# LED.net
KiCad netlist of a schematic drawn in EAGLE
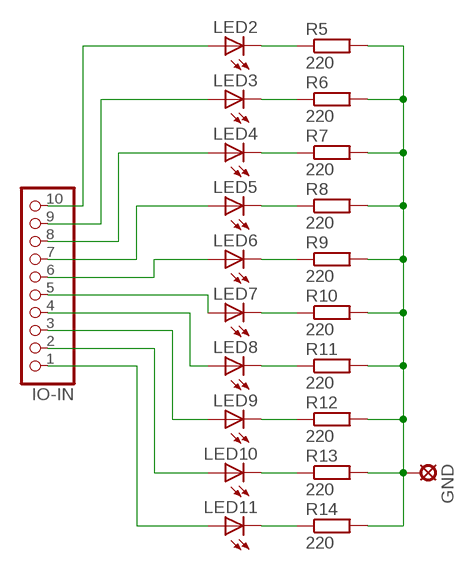
[diagram p0: schematic, sheet 1]

(export (version "E")
  (design (tool "Eeschema 10.0.6"))
  (components
    (comp (ref "GND")
      (value "LSP10")
      (footprint "eagle-import:LSP10")
      (libsource (lib "eagle-import") (part "LSP10"))
    )
    (comp (ref "IO-IN")
      (value "PINHD-1X10")
      (footprint "eagle-import:1X10")
      (libsource (lib "eagle-import") (part "PINHD-1X10"))
    )
    (comp (ref "LED2")
      (value "LED3MM")
      (footprint "eagle-import:LED3MM")
      (libsource (lib "eagle-import") (part "LED3MM"))
    )
    (comp (ref "LED3")
      (value "LED3MM")
      (footprint "eagle-import:LED3MM")
      (libsource (lib "eagle-import") (part "LED3MM"))
    )
    (comp (ref "LED4")
      (value "LED3MM")
      (footprint "eagle-import:LED3MM")
      (libsource (lib "eagle-import") (part "LED3MM"))
    )
    (comp (ref "LED5")
      (value "LED3MM")
      (footprint "eagle-import:LED3MM")
      (libsource (lib "eagle-import") (part "LED3MM"))
    )
    (comp (ref "LED6")
      (value "LED3MM")
      (footprint "eagle-import:LED3MM")
      (libsource (lib "eagle-import") (part "LED3MM"))
    )
    (comp (ref "LED7")
      (value "LED3MM")
      (footprint "eagle-import:LED3MM")
      (libsource (lib "eagle-import") (part "LED3MM"))
    )
    (comp (ref "LED8")
      (value "LED3MM")
      (footprint "eagle-import:LED3MM")
      (libsource (lib "eagle-import") (part "LED3MM"))
    )
    (comp (ref "LED9")
      (value "LED3MM")
      (footprint "eagle-import:LED3MM")
      (libsource (lib "eagle-import") (part "LED3MM"))
    )
    (comp (ref "LED10")
      (value "LED3MM")
      (footprint "eagle-import:LED3MM")
      (libsource (lib "eagle-import") (part "LED3MM"))
    )
    (comp (ref "LED11")
      (value "LED3MM")
      (footprint "eagle-import:LED3MM")
      (libsource (lib "eagle-import") (part "LED3MM"))
    )
    (comp (ref "R5")
      (value "220")
      (footprint "eagle-import:0207_10")
      (libsource (lib "eagle-import") (part "R-EU_0207/10"))
    )
    (comp (ref "R6")
      (value "220")
      (footprint "eagle-import:0207_10")
      (libsource (lib "eagle-import") (part "R-EU_0207/10"))
    )
    (comp (ref "R7")
      (value "220")
      (footprint "eagle-import:0207_10")
      (libsource (lib "eagle-import") (part "R-EU_0207/10"))
    )
    (comp (ref "R8")
      (value "220")
      (footprint "eagle-import:0207_10")
      (libsource (lib "eagle-import") (part "R-EU_0207/10"))
    )
    (comp (ref "R9")
      (value "220")
      (footprint "eagle-import:0207_10")
      (libsource (lib "eagle-import") (part "R-EU_0207/10"))
    )
    (comp (ref "R10")
      (value "220")
      (footprint "eagle-import:0207_10")
      (libsource (lib "eagle-import") (part "R-EU_0207/10"))
    )
    (comp (ref "R11")
      (value "220")
      (footprint "eagle-import:0207_10")
      (libsource (lib "eagle-import") (part "R-EU_0207/10"))
    )
    (comp (ref "R12")
      (value "220")
      (footprint "eagle-import:0207_10")
      (libsource (lib "eagle-import") (part "R-EU_0207/10"))
    )
    (comp (ref "R13")
      (value "220")
      (footprint "eagle-import:0207_10")
      (libsource (lib "eagle-import") (part "R-EU_0207/10"))
    )
    (comp (ref "R14")
      (value "220")
      (footprint "eagle-import:0207_10")
      (libsource (lib "eagle-import") (part "R-EU_0207/10"))
    )
  )
  (nets
    (net (code "1") (name "Net-(GND-PadMP)") (class "Default")
      (node (ref "GND") (pin "MP") (pinfunction "MP_MP") (pintype "passive"))
      (node (ref "R10") (pin "2") (pinfunction "2_2") (pintype "passive"))
      (node (ref "R11") (pin "2") (pinfunction "2_2") (pintype "passive"))
      (node (ref "R12") (pin "2") (pinfunction "2_2") (pintype "passive"))
      (node (ref "R13") (pin "2") (pinfunction "2_2") (pintype "passive"))
      (node (ref "R14") (pin "2") (pinfunction "2_2") (pintype "passive"))
      (node (ref "R5") (pin "2") (pinfunction "2_2") (pintype "passive"))
      (node (ref "R6") (pin "2") (pinfunction "2_2") (pintype "passive"))
      (node (ref "R7") (pin "2") (pinfunction "2_2") (pintype "passive"))
      (node (ref "R8") (pin "2") (pinfunction "2_2") (pintype "passive"))
      (node (ref "R9") (pin "2") (pinfunction "2_2") (pintype "passive"))
    )
    (net (code "2") (name "Net-(IO-IN-Pad1)") (class "Default")
      (node (ref "IO-IN") (pin "1") (pinfunction "1_1") (pintype "passive"))
      (node (ref "LED11") (pin "A") (pinfunction "A_A") (pintype "passive"))
    )
    (net (code "3") (name "Net-(IO-IN-Pad2)") (class "Default")
      (node (ref "IO-IN") (pin "2") (pinfunction "2_2") (pintype "passive"))
      (node (ref "LED10") (pin "A") (pinfunction "A_A") (pintype "passive"))
    )
    (net (code "4") (name "Net-(IO-IN-Pad3)") (class "Default")
      (node (ref "IO-IN") (pin "3") (pinfunction "3_3") (pintype "passive"))
      (node (ref "LED9") (pin "A") (pinfunction "A_A") (pintype "passive"))
    )
    (net (code "5") (name "Net-(IO-IN-Pad4)") (class "Default")
      (node (ref "IO-IN") (pin "4") (pinfunction "4_4") (pintype "passive"))
      (node (ref "LED8") (pin "A") (pinfunction "A_A") (pintype "passive"))
    )
    (net (code "6") (name "Net-(IO-IN-Pad5)") (class "Default")
      (node (ref "IO-IN") (pin "5") (pinfunction "5_5") (pintype "passive"))
      (node (ref "LED7") (pin "A") (pinfunction "A_A") (pintype "passive"))
    )
    (net (code "7") (name "Net-(IO-IN-Pad6)") (class "Default")
      (node (ref "IO-IN") (pin "6") (pinfunction "6_6") (pintype "passive"))
      (node (ref "LED6") (pin "A") (pinfunction "A_A") (pintype "passive"))
    )
    (net (code "8") (name "Net-(IO-IN-Pad7)") (class "Default")
      (node (ref "IO-IN") (pin "7") (pinfunction "7_7") (pintype "passive"))
      (node (ref "LED5") (pin "A") (pinfunction "A_A") (pintype "passive"))
    )
    (net (code "9") (name "Net-(IO-IN-Pad8)") (class "Default")
      (node (ref "IO-IN") (pin "8") (pinfunction "8_8") (pintype "passive"))
      (node (ref "LED4") (pin "A") (pinfunction "A_A") (pintype "passive"))
    )
    (net (code "10") (name "Net-(IO-IN-Pad9)") (class "Default")
      (node (ref "IO-IN") (pin "9") (pinfunction "9_9") (pintype "passive"))
      (node (ref "LED3") (pin "A") (pinfunction "A_A") (pintype "passive"))
    )
    (net (code "11") (name "Net-(IO-IN-Pad10)") (class "Default")
      (node (ref "IO-IN") (pin "10") (pinfunction "10_10") (pintype "passive"))
      (node (ref "LED2") (pin "A") (pinfunction "A_A") (pintype "passive"))
    )
    (net (code "12") (name "Net-(LED2-C)") (class "Default")
      (node (ref "LED2") (pin "K") (pinfunction "C_K") (pintype "passive"))
      (node (ref "R5") (pin "1") (pinfunction "1_1") (pintype "passive"))
    )
    (net (code "13") (name "Net-(LED3-C)") (class "Default")
      (node (ref "LED3") (pin "K") (pinfunction "C_K") (pintype "passive"))
      (node (ref "R6") (pin "1") (pinfunction "1_1") (pintype "passive"))
    )
    (net (code "14") (name "Net-(LED4-C)") (class "Default")
      (node (ref "LED4") (pin "K") (pinfunction "C_K") (pintype "passive"))
      (node (ref "R7") (pin "1") (pinfunction "1_1") (pintype "passive"))
    )
    (net (code "15") (name "Net-(LED5-C)") (class "Default")
      (node (ref "LED5") (pin "K") (pinfunction "C_K") (pintype "passive"))
      (node (ref "R8") (pin "1") (pinfunction "1_1") (pintype "passive"))
    )
    (net (code "16") (name "Net-(LED6-C)") (class "Default")
      (node (ref "LED6") (pin "K") (pinfunction "C_K") (pintype "passive"))
      (node (ref "R9") (pin "1") (pinfunction "1_1") (pintype "passive"))
    )
    (net (code "17") (name "Net-(LED7-C)") (class "Default")
      (node (ref "LED7") (pin "K") (pinfunction "C_K") (pintype "passive"))
      (node (ref "R10") (pin "1") (pinfunction "1_1") (pintype "passive"))
    )
    (net (code "18") (name "Net-(LED8-C)") (class "Default")
      (node (ref "LED8") (pin "K") (pinfunction "C_K") (pintype "passive"))
      (node (ref "R11") (pin "1") (pinfunction "1_1") (pintype "passive"))
    )
    (net (code "19") (name "Net-(LED9-C)") (class "Default")
      (node (ref "LED9") (pin "K") (pinfunction "C_K") (pintype "passive"))
      (node (ref "R12") (pin "1") (pinfunction "1_1") (pintype "passive"))
    )
    (net (code "20") (name "Net-(LED10-C)") (class "Default")
      (node (ref "LED10") (pin "K") (pinfunction "C_K") (pintype "passive"))
      (node (ref "R13") (pin "1") (pinfunction "1_1") (pintype "passive"))
    )
    (net (code "21") (name "Net-(LED11-C)") (class "Default")
      (node (ref "LED11") (pin "K") (pinfunction "C_K") (pintype "passive"))
      (node (ref "R14") (pin "1") (pinfunction "1_1") (pintype "passive"))
    )
  )
)
